# drv8305_instaspin_driver.net
KiCad netlist of a schematic drawn in Altium Designer
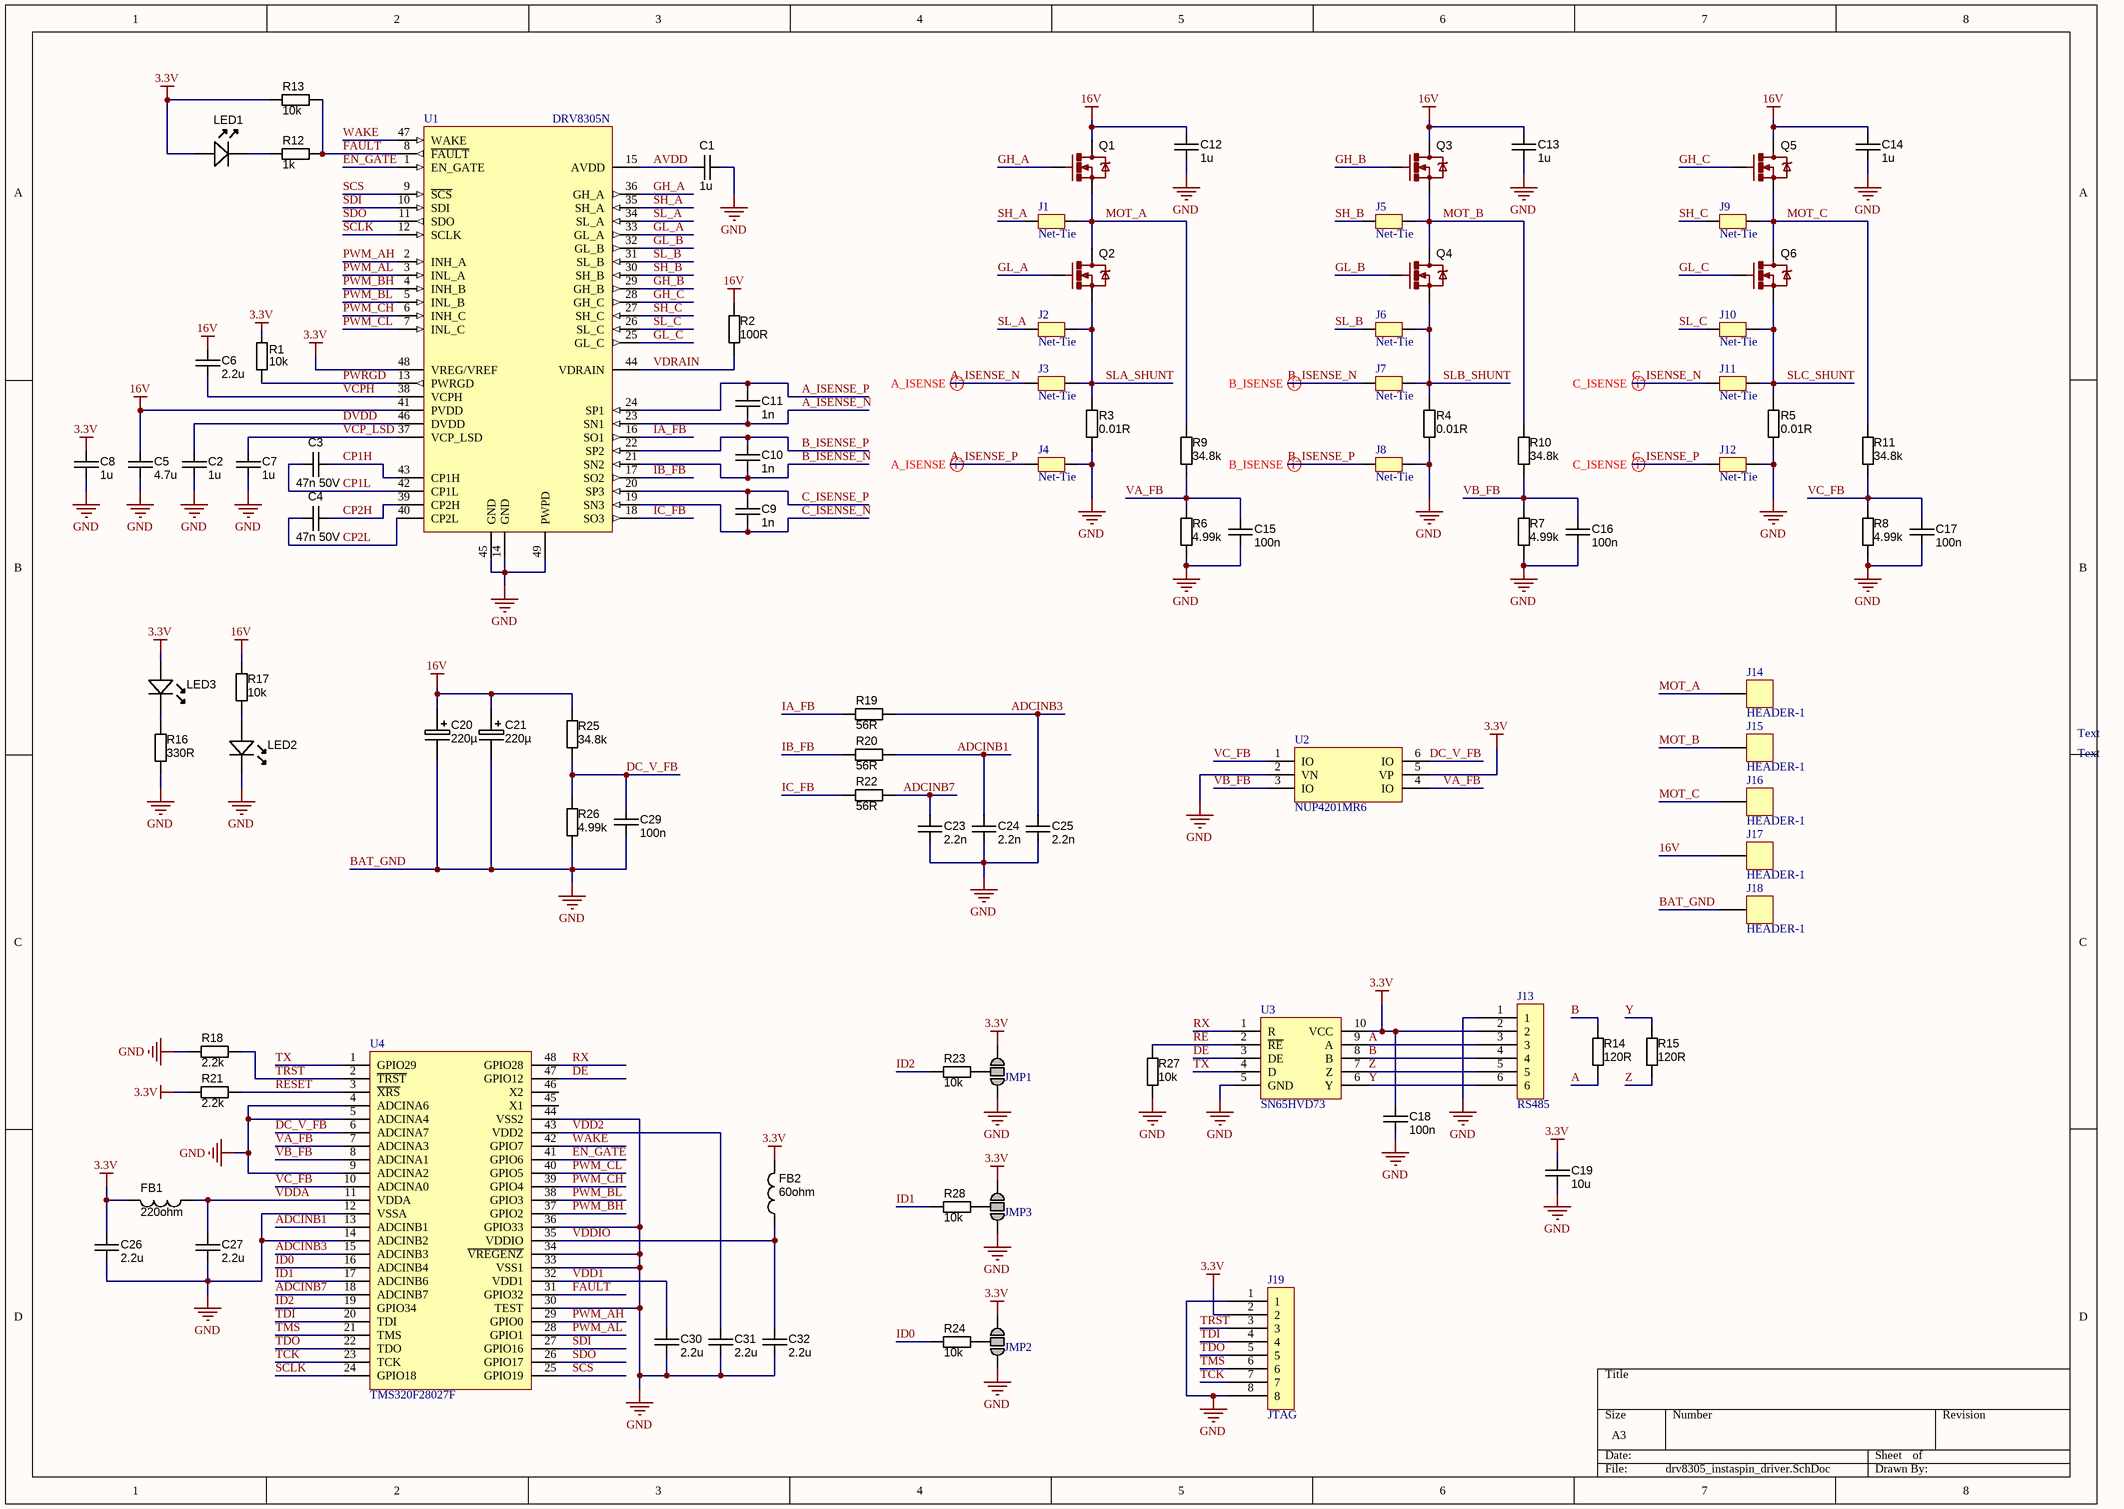
[diagram p0: drv8305_instaspin_driver.SchDoc]

(export (version "E")
  (design (tool "Eeschema 10.0.6"))
  (components
    (comp (ref "C1")
      (value "1u")
      (footprint "CAPC1608X90N")
      (description "Capacitor SMD Cer 1uF 10% 16V X7R 0603")
      (fields (field (name "TOLERANCE") "±10%"))
      (libsource (lib "PBL - Capacitors") (part "CAPC_1u_0603_X7R_16V_10%"))
    )
    (comp (ref "C2")
      (value "1u")
      (footprint "CAPC1608X90N")
      (description "Capacitor SMD Cer 1uF 10% 16V X7R 0603")
      (fields (field (name "TOLERANCE") "±10%"))
      (libsource (lib "PBL - Capacitors") (part "CAPC_1u_0603_X7R_16V_10%"))
    )
    (comp (ref "C3")
      (value "47n 50V")
      (footprint "CAPC1608X90N")
      (description "Capacitor SMD Cer 1uF 10% 16V X7R 0603")
      (fields (field (name "TOLERANCE") "±10%"))
      (libsource (lib "PBL - Capacitors") (part "CAPC_1u_0603_X7R_16V_10%"))
    )
    (comp (ref "C4")
      (value "47n 50V")
      (footprint "CAPC1608X90N")
      (description "Capacitor SMD Cer 1uF 10% 16V X7R 0603")
      (fields (field (name "TOLERANCE") "±10%"))
      (libsource (lib "PBL - Capacitors") (part "CAPC_1u_0603_X7R_16V_10%"))
    )
    (comp (ref "C5")
      (value "4.7u")
      (footprint "CAPC3216X180N")
      (description "Capacitor SMD Cer 6.8nF 5% 50V NP0 1206")
      (fields (field (name "TOLERANCE") "±5%"))
      (libsource (lib "PBL - Capacitors") (part "CAPC_6n8_1206_NP0_50V"))
    )
    (comp (ref "C6")
      (value "2.2u")
      (footprint "CAPC3216X180N")
      (description "Capacitor SMD Cer 6.8nF 5% 50V NP0 1206")
      (fields (field (name "TOLERANCE") "±5%"))
      (libsource (lib "PBL - Capacitors") (part "CAPC_6n8_1206_NP0_50V"))
    )
    (comp (ref "C7")
      (value "1u")
      (footprint "CAPC1608X90N")
      (description "Capacitor SMD Cer 1uF 10% 16V X7R 0603")
      (fields (field (name "TOLERANCE") "±10%"))
      (libsource (lib "PBL - Capacitors") (part "CAPC_1u_0603_X7R_16V_10%"))
    )
    (comp (ref "C8")
      (value "1u")
      (footprint "CAPC1608X90N")
      (description "Capacitor SMD Cer 1uF 10% 16V X7R 0603")
      (fields (field (name "TOLERANCE") "±10%"))
      (libsource (lib "PBL - Capacitors") (part "CAPC_1u_0603_X7R_16V_10%"))
    )
    (comp (ref "C9")
      (value "1n")
      (footprint "CAPC1608X90N")
      (description "Capacitor SMD Cer 1uF 10% 16V X7R 0603")
      (fields (field (name "TOLERANCE") "±10%"))
      (libsource (lib "PBL - Capacitors") (part "CAPC_1u_0603_X7R_16V_10%"))
    )
    (comp (ref "C10")
      (value "1n")
      (footprint "CAPC1608X90N")
      (description "Capacitor SMD Cer 1uF 10% 16V X7R 0603")
      (fields (field (name "TOLERANCE") "±10%"))
      (libsource (lib "PBL - Capacitors") (part "CAPC_1u_0603_X7R_16V_10%"))
    )
    (comp (ref "C11")
      (value "1n")
      (footprint "CAPC1608X90N")
      (description "Capacitor SMD Cer 1uF 10% 16V X7R 0603")
      (fields (field (name "TOLERANCE") "±10%"))
      (libsource (lib "PBL - Capacitors") (part "CAPC_1u_0603_X7R_16V_10%"))
    )
    (comp (ref "C12")
      (value "1u")
      (footprint "CAPC1608X90N")
      (description "Capacitor SMD Cer 1uF 10% 16V X7R 0603")
      (fields (field (name "TOLERANCE") "±10%"))
      (libsource (lib "PBL - Capacitors") (part "CAPC_1u_0603_X7R_16V_10%"))
    )
    (comp (ref "C13")
      (value "1u")
      (footprint "CAPC1608X90N")
      (description "Capacitor SMD Cer 1uF 10% 16V X7R 0603")
      (fields (field (name "TOLERANCE") "±10%"))
      (libsource (lib "PBL - Capacitors") (part "CAPC_1u_0603_X7R_16V_10%"))
    )
    (comp (ref "C14")
      (value "1u")
      (footprint "CAPC1608X90N")
      (description "Capacitor SMD Cer 1uF 10% 16V X7R 0603")
      (fields (field (name "TOLERANCE") "±10%"))
      (libsource (lib "PBL - Capacitors") (part "CAPC_1u_0603_X7R_16V_10%"))
    )
    (comp (ref "C15")
      (value "100n")
      (footprint "CAPC1608X90N")
      (description "Capacitor SMD Cer 1uF 10% 16V X7R 0603")
      (fields (field (name "TOLERANCE") "±10%"))
      (libsource (lib "PBL - Capacitors") (part "CAPC_1u_0603_X7R_16V_10%"))
    )
    (comp (ref "C16")
      (value "100n")
      (footprint "CAPC1608X90N")
      (description "Capacitor SMD Cer 1uF 10% 16V X7R 0603")
      (fields (field (name "TOLERANCE") "±10%"))
      (libsource (lib "PBL - Capacitors") (part "CAPC_1u_0603_X7R_16V_10%"))
    )
    (comp (ref "C17")
      (value "100n")
      (footprint "CAPC1608X90N")
      (description "Capacitor SMD Cer 1uF 10% 16V X7R 0603")
      (fields (field (name "TOLERANCE") "±10%"))
      (libsource (lib "PBL - Capacitors") (part "CAPC_1u_0603_X7R_16V_10%"))
    )
    (comp (ref "C18")
      (value "100n")
      (footprint "CAPC1608X90N")
      (description "Capacitor SMD Cer 1uF 10% 16V X7R 0603")
      (fields (field (name "TOLERANCE") "±10%"))
      (libsource (lib "PBL - Capacitors") (part "CAPC_1u_0603_X7R_16V_10%"))
    )
    (comp (ref "C19")
      (value "10u")
      (footprint "CAPC3216X180N")
      (description "Capacitor SMD Cer 1uF 10% 16V X7R 0603")
      (fields (field (name "TOLERANCE") "±10%"))
      (libsource (lib "PBL - Capacitors") (part "CAPC_1u_0603_X7R_16V_10%"))
    )
    (comp (ref "C20")
      (value "220µ")
      (footprint "CAP_ELEC_6.3x4.2")
      (description "Capacitor THT Alum Elec 470uF 20% 16V")
      (fields (field (name "TOLERANCE") "±20%"))
      (libsource (lib "PBL - Capacitors") (part "CAPE_470u_16V_THT"))
    )
    (comp (ref "C21")
      (value "220µ")
      (footprint "CAP_ELEC_6.3x4.2")
      (description "Capacitor THT Alum Elec 470uF 20% 16V")
      (fields (field (name "TOLERANCE") "±20%"))
      (libsource (lib "PBL - Capacitors") (part "CAPE_470u_16V_THT"))
    )
    (comp (ref "C23")
      (value "2.2n")
      (footprint "CAPC1608X90N")
      (description "Capacitor SMD Cer 1uF 10% 16V X7R 0603")
      (fields (field (name "TOLERANCE") "±10%"))
      (libsource (lib "PBL - Capacitors") (part "CAPC_1u_0603_X7R_16V_10%"))
    )
    (comp (ref "C24")
      (value "2.2n")
      (footprint "CAPC1608X90N")
      (description "Capacitor SMD Cer 1uF 10% 16V X7R 0603")
      (fields (field (name "TOLERANCE") "±10%"))
      (libsource (lib "PBL - Capacitors") (part "CAPC_1u_0603_X7R_16V_10%"))
    )
    (comp (ref "C25")
      (value "2.2n")
      (footprint "CAPC1608X90N")
      (description "Capacitor SMD Cer 1uF 10% 16V X7R 0603")
      (fields (field (name "TOLERANCE") "±10%"))
      (libsource (lib "PBL - Capacitors") (part "CAPC_1u_0603_X7R_16V_10%"))
    )
    (comp (ref "C26")
      (value "2.2u")
      (footprint "CAPC1608X90N")
      (description "Capacitor SMD Cer 1uF 10% 16V X7R 0603")
      (fields (field (name "TOLERANCE") "±10%"))
      (libsource (lib "PBL - Capacitors") (part "CAPC_1u_0603_X7R_16V_10%"))
    )
    (comp (ref "C27")
      (value "2.2u")
      (footprint "CAPC1608X90N")
      (description "Capacitor SMD Cer 1uF 10% 16V X7R 0603")
      (fields (field (name "TOLERANCE") "±10%"))
      (libsource (lib "PBL - Capacitors") (part "CAPC_1u_0603_X7R_16V_10%"))
    )
    (comp (ref "C29")
      (value "100n")
      (footprint "CAPC1608X90N")
      (description "Capacitor SMD Cer 1uF 10% 16V X7R 0603")
      (fields (field (name "TOLERANCE") "±10%"))
      (libsource (lib "PBL - Capacitors") (part "CAPC_1u_0603_X7R_16V_10%"))
    )
    (comp (ref "C30")
      (value "2.2u")
      (footprint "CAPC1608X90N")
      (description "Capacitor SMD Cer 1uF 10% 16V X7R 0603")
      (fields (field (name "TOLERANCE") "±10%"))
      (libsource (lib "PBL - Capacitors") (part "CAPC_1u_0603_X7R_16V_10%"))
    )
    (comp (ref "C31")
      (value "2.2u")
      (footprint "CAPC1608X90N")
      (description "Capacitor SMD Cer 1uF 10% 16V X7R 0603")
      (fields (field (name "TOLERANCE") "±10%"))
      (libsource (lib "PBL - Capacitors") (part "CAPC_1u_0603_X7R_16V_10%"))
    )
    (comp (ref "C32")
      (value "2.2u")
      (footprint "CAPC1608X90N")
      (description "Capacitor SMD Cer 1uF 10% 16V X7R 0603")
      (fields (field (name "TOLERANCE") "±10%"))
      (libsource (lib "PBL - Capacitors") (part "CAPC_1u_0603_X7R_16V_10%"))
    )
    (comp (ref "FB1")
      (value "220ohm")
      (footprint "INDC1608N")
      (description "Ferrite bead 120 Ohm at 100 MHz 2A 0603 SMD")
      (libsource (lib "PBL - Inductors") (part "FERRITE_120R-100MHz_0603"))
    )
    (comp (ref "FB2")
      (value "60ohm")
      (footprint "INDC1608N")
      (description "Ferrite bead 120 Ohm at 100 MHz 2A 0603 SMD")
      (libsource (lib "PBL - Inductors") (part "FERRITE_120R-100MHz_0603"))
    )
    (comp (ref "J1")
      (value "Net-Tie")
      (footprint "NET-TIE-0602")
      (libsource (lib "connectors") (part "Net-Tie"))
    )
    (comp (ref "J2")
      (value "Net-Tie")
      (footprint "NET-TIE-0602")
      (libsource (lib "connectors") (part "Net-Tie"))
    )
    (comp (ref "J3")
      (value "Net-Tie")
      (footprint "NET-TIE-0602")
      (libsource (lib "connectors") (part "Net-Tie"))
    )
    (comp (ref "J4")
      (value "Net-Tie")
      (footprint "NET-TIE-0602")
      (libsource (lib "connectors") (part "Net-Tie"))
    )
    (comp (ref "J5")
      (value "Net-Tie")
      (footprint "NET-TIE-0602")
      (libsource (lib "connectors") (part "Net-Tie"))
    )
    (comp (ref "J6")
      (value "Net-Tie")
      (footprint "NET-TIE-0602")
      (libsource (lib "connectors") (part "Net-Tie"))
    )
    (comp (ref "J7")
      (value "Net-Tie")
      (footprint "NET-TIE-0602")
      (libsource (lib "connectors") (part "Net-Tie"))
    )
    (comp (ref "J8")
      (value "Net-Tie")
      (footprint "NET-TIE-0602")
      (libsource (lib "connectors") (part "Net-Tie"))
    )
    (comp (ref "J9")
      (value "Net-Tie")
      (footprint "NET-TIE-0602")
      (libsource (lib "connectors") (part "Net-Tie"))
    )
    (comp (ref "J10")
      (value "Net-Tie")
      (footprint "NET-TIE-0602")
      (libsource (lib "connectors") (part "Net-Tie"))
    )
    (comp (ref "J11")
      (value "Net-Tie")
      (footprint "NET-TIE-0602")
      (libsource (lib "connectors") (part "Net-Tie"))
    )
    (comp (ref "J12")
      (value "Net-Tie")
      (footprint "NET-TIE-0602")
      (libsource (lib "connectors") (part "Net-Tie"))
    )
    (comp (ref "J13")
      (value "RS485")
      (footprint "MICRO-MATCH-6")
      (libsource (lib "connectors") (part "HEADER-6"))
    )
    (comp (ref "J14")
      (value "HEADER-1")
      (footprint "2MM-BANANA-VIA-BOTTOM-PAD")
      (libsource (lib "connectors") (part "HEADER-1"))
    )
    (comp (ref "J15")
      (value "HEADER-1")
      (footprint "2MM-BANANA-VIA-BOTTOM-PAD")
      (libsource (lib "connectors") (part "HEADER-1"))
    )
    (comp (ref "J16")
      (value "HEADER-1")
      (footprint "2MM-BANANA-VIA-BOTTOM-PAD")
      (libsource (lib "connectors") (part "HEADER-1"))
    )
    (comp (ref "J17")
      (value "HEADER-1")
      (footprint "2MM-BANANA-VIA-BOTTOM-PAD")
      (libsource (lib "connectors") (part "HEADER-1"))
    )
    (comp (ref "J18")
      (value "HEADER-1")
      (footprint "2MM-BANANA-VIA-BOTTOM-PAD")
      (libsource (lib "connectors") (part "HEADER-1"))
    )
    (comp (ref "J19")
      (value "JTAG")
      (footprint "MICRO-MATCH-8")
      (libsource (lib "connectors") (part "HEADER-8"))
    )
    (comp (ref "JMP1")
      (value "JUMPER")
      (footprint "JUMPER-SMD-3WAY-0303")
      (libsource (lib "connectors") (part "JUMPER-SMD-3WAY"))
    )
    (comp (ref "JMP2")
      (value "JUMPER")
      (footprint "JUMPER-SMD-3WAY-0303")
      (libsource (lib "connectors") (part "JUMPER-SMD-3WAY"))
    )
    (comp (ref "JMP3")
      (value "JUMPER")
      (footprint "JUMPER-SMD-3WAY-0303")
      (libsource (lib "connectors") (part "JUMPER-SMD-3WAY"))
    )
    (comp (ref "LED1")
      (value "LED Orange")
      (footprint "LED-0603-GREEN")
      (description "LED 0603 SMD Green 525nm 350mcd 20mA")
      (libsource (lib "PBL - Light Sources") (part "LED_SMD_Green_0603_525nm_350mcd"))
    )
    (comp (ref "LED2")
      (value "LED White")
      (footprint "LED-0603-GREEN")
      (description "LED 0603 SMD Green 525nm 350mcd 20mA")
      (libsource (lib "PBL - Light Sources") (part "LED_SMD_Green_0603_525nm_350mcd"))
    )
    (comp (ref "LED3")
      (value "LED White")
      (footprint "LED-0603-GREEN")
      (description "LED 0603 SMD Green 525nm 350mcd 20mA")
      (libsource (lib "PBL - Light Sources") (part "LED_SMD_Green_0603_525nm_350mcd"))
    )
    (comp (ref "Q1") (value "MOSFET-N") (footprint "SOT669") (libsource (lib "mosfets") (part "MOSFET-N")))
    (comp (ref "Q2") (value "MOSFET-N") (footprint "SOT669") (libsource (lib "mosfets") (part "MOSFET-N")))
    (comp (ref "Q3") (value "MOSFET-N") (footprint "SOT669") (libsource (lib "mosfets") (part "MOSFET-N")))
    (comp (ref "Q4") (value "MOSFET-N") (footprint "SOT669") (libsource (lib "mosfets") (part "MOSFET-N")))
    (comp (ref "Q5") (value "MOSFET-N") (footprint "SOT669") (libsource (lib "mosfets") (part "MOSFET-N")))
    (comp (ref "Q6") (value "MOSFET-N") (footprint "SOT669") (libsource (lib "mosfets") (part "MOSFET-N")))
    (comp (ref "R1")
      (value "10k")
      (footprint "RESC1608X55N")
      (description "Resistor SMD chip 1.5k Ohm 0.1W 5% 0603")
      (fields (field (name "TOLERANCE") "±5%"))
      (libsource (lib "") (part "RES_1K5_0603_5%_3"))
    )
    (comp (ref "R2")
      (value "100R")
      (footprint "RESC1608X55N")
      (description "Resistor SMD chip 1.5k Ohm 0.1W 5% 0603")
      (fields (field (name "TOLERANCE") "±5%"))
      (libsource (lib "PBL - Resistors") (part "RES_1K5_0603_5%"))
    )
    (comp (ref "R3")
      (value "0.01R")
      (footprint "RESC6332X70N")
      (description "Resistor SMD chip 3.3k Ohm 1W 5% 2512")
      (fields (field (name "TOLERANCE") "±5%"))
      (libsource (lib "PBL - Resistors") (part "RES_3K3_2512_5%"))
    )
    (comp (ref "R4")
      (value "0.01R")
      (footprint "RESC6332X70N")
      (description "Resistor SMD chip 3.3k Ohm 1W 5% 2512")
      (fields (field (name "TOLERANCE") "±5%"))
      (libsource (lib "PBL - Resistors") (part "RES_3K3_2512_5%"))
    )
    (comp (ref "R5")
      (value "0.01R")
      (footprint "RESC6332X70N")
      (description "Resistor SMD chip 3.3k Ohm 1W 5% 2512")
      (fields (field (name "TOLERANCE") "±5%"))
      (libsource (lib "PBL - Resistors") (part "RES_3K3_2512_5%"))
    )
    (comp (ref "R6")
      (value "4.99k")
      (footprint "RESC1608X55N")
      (description "Resistor SMD chip 1.5k Ohm 0.1W 5% 0603")
      (fields (field (name "TOLERANCE") "±5%"))
      (libsource (lib "PBL - Resistors") (part "RES_1K5_0603_5%"))
    )
    (comp (ref "R7")
      (value "4.99k")
      (footprint "RESC1608X55N")
      (description "Resistor SMD chip 1.5k Ohm 0.1W 5% 0603")
      (fields (field (name "TOLERANCE") "±5%"))
      (libsource (lib "PBL - Resistors") (part "RES_1K5_0603_5%"))
    )
    (comp (ref "R8")
      (value "4.99k")
      (footprint "RESC1608X55N")
      (description "Resistor SMD chip 1.5k Ohm 0.1W 5% 0603")
      (fields (field (name "TOLERANCE") "±5%"))
      (libsource (lib "PBL - Resistors") (part "RES_1K5_0603_5%"))
    )
    (comp (ref "R9")
      (value "34.8k")
      (footprint "RESC1608X55N")
      (description "Resistor SMD chip 1.5k Ohm 0.1W 5% 0603")
      (fields (field (name "TOLERANCE") "±5%"))
      (libsource (lib "PBL - Resistors") (part "RES_1K5_0603_5%"))
    )
    (comp (ref "R10")
      (value "34.8k")
      (footprint "RESC1608X55N")
      (description "Resistor SMD chip 1.5k Ohm 0.1W 5% 0603")
      (fields (field (name "TOLERANCE") "±5%"))
      (libsource (lib "PBL - Resistors") (part "RES_1K5_0603_5%"))
    )
    (comp (ref "R11")
      (value "34.8k")
      (footprint "RESC1608X55N")
      (description "Resistor SMD chip 1.5k Ohm 0.1W 5% 0603")
      (fields (field (name "TOLERANCE") "±5%"))
      (libsource (lib "PBL - Resistors") (part "RES_1K5_0603_5%"))
    )
    (comp (ref "R12")
      (value "1k")
      (footprint "RESC1608X55N")
      (description "Resistor SMD chip 1.5k Ohm 0.1W 5% 0603")
      (fields (field (name "TOLERANCE") "±5%"))
      (libsource (lib "") (part "RES_1K5_0603_5%_2"))
    )
    (comp (ref "R13")
      (value "10k")
      (footprint "RESC1608X55N")
      (description "Resistor SMD chip 1.5k Ohm 0.1W 5% 0603")
      (fields (field (name "TOLERANCE") "±5%"))
      (libsource (lib "") (part "RES_1K5_0603_5%_2"))
    )
    (comp (ref "R14")
      (value "120R")
      (footprint "RESC1608X55N")
      (description "Resistor SMD chip 1.5k Ohm 0.1W 5% 0603")
      (fields (field (name "TOLERANCE") "±5%"))
      (libsource (lib "PBL - Resistors") (part "RES_1K5_0603_5%"))
    )
    (comp (ref "R15")
      (value "120R")
      (footprint "RESC1608X55N")
      (description "Resistor SMD chip 1.5k Ohm 0.1W 5% 0603")
      (fields (field (name "TOLERANCE") "±5%"))
      (libsource (lib "PBL - Resistors") (part "RES_1K5_0603_5%"))
    )
    (comp (ref "R16")
      (value "330R")
      (footprint "RESC1608X55N")
      (description "Resistor SMD chip 1.5k Ohm 0.1W 5% 0603")
      (fields (field (name "TOLERANCE") "±5%"))
      (libsource (lib "PBL - Resistors") (part "RES_1K5_0603_5%"))
    )
    (comp (ref "R17")
      (value "10k")
      (footprint "RESC1608X55N")
      (description "Resistor SMD chip 1.5k Ohm 0.1W 5% 0603")
      (fields (field (name "TOLERANCE") "±5%"))
      (libsource (lib "PBL - Resistors") (part "RES_1K5_0603_5%"))
    )
    (comp (ref "R18")
      (value "2.2k")
      (footprint "RESC1608X55N")
      (description "Resistor SMD chip 1.5k Ohm 0.1W 5% 0603")
      (fields (field (name "TOLERANCE") "±5%"))
      (libsource (lib "") (part "RES_1K5_0603_5%_2"))
    )
    (comp (ref "R19")
      (value "56R")
      (footprint "RESC1608X55N")
      (description "Resistor SMD chip 1.5k Ohm 0.1W 5% 0603")
      (fields (field (name "TOLERANCE") "±5%"))
      (libsource (lib "") (part "RES_1K5_0603_5%_1"))
    )
    (comp (ref "R20")
      (value "56R")
      (footprint "RESC1608X55N")
      (description "Resistor SMD chip 1.5k Ohm 0.1W 5% 0603")
      (fields (field (name "TOLERANCE") "±5%"))
      (libsource (lib "") (part "RES_1K5_0603_5%_1"))
    )
    (comp (ref "R21")
      (value "2.2k")
      (footprint "RESC1608X55N")
      (description "Resistor SMD chip 1.5k Ohm 0.1W 5% 0603")
      (fields (field (name "TOLERANCE") "±5%"))
      (libsource (lib "") (part "RES_1K5_0603_5%_1"))
    )
    (comp (ref "R22")
      (value "56R")
      (footprint "RESC1608X55N")
      (description "Resistor SMD chip 1.5k Ohm 0.1W 5% 0603")
      (fields (field (name "TOLERANCE") "±5%"))
      (libsource (lib "") (part "RES_1K5_0603_5%_1"))
    )
    (comp (ref "R23")
      (value "10k")
      (footprint "RESC1608X55N")
      (description "Resistor SMD chip 1.5k Ohm 0.1W 5% 0603")
      (fields (field (name "TOLERANCE") "±5%"))
      (libsource (lib "") (part "RES_1K5_0603_5%_1"))
    )
    (comp (ref "R24")
      (value "10k")
      (footprint "RESC1608X55N")
      (description "Resistor SMD chip 1.5k Ohm 0.1W 5% 0603")
      (fields (field (name "TOLERANCE") "±5%"))
      (libsource (lib "") (part "RES_1K5_0603_5%_1"))
    )
    (comp (ref "R25")
      (value "34.8k")
      (footprint "RESC1608X55N")
      (description "Resistor SMD chip 1.5k Ohm 0.1W 5% 0603")
      (fields (field (name "TOLERANCE") "±5%"))
      (libsource (lib "PBL - Resistors") (part "RES_1K5_0603_5%"))
    )
    (comp (ref "R26")
      (value "4.99k")
      (footprint "RESC1608X55N")
      (description "Resistor SMD chip 1.5k Ohm 0.1W 5% 0603")
      (fields (field (name "TOLERANCE") "±5%"))
      (libsource (lib "PBL - Resistors") (part "RES_1K5_0603_5%"))
    )
    (comp (ref "R27")
      (value "10k")
      (footprint "RESC1608X55N")
      (description "Resistor SMD chip 1.5k Ohm 0.1W 5% 0603")
      (fields (field (name "TOLERANCE") "±5%"))
      (libsource (lib "") (part "RES_1K5_0603_5%_3"))
    )
    (comp (ref "R28")
      (value "10k")
      (footprint "RESC1608X55N")
      (description "Resistor SMD chip 1.5k Ohm 0.1W 5% 0603")
      (fields (field (name "TOLERANCE") "±5%"))
      (libsource (lib "") (part "RES_1K5_0603_5%_1"))
    )
    (comp (ref "U1")
      (value "DRV8305N")
      (footprint "PQFP48_PAD")
      (libsource (lib "texas_instruments") (part "DRV8305"))
    )
    (comp (ref "U2")
      (value "NUP4201MR6")
      (footprint "TSOP-6")
      (libsource (lib "digital") (part "NUP4201MR6"))
    )
    (comp (ref "U3")
      (value "SN65HVD73")
      (footprint "SOP10")
      (libsource (lib "texas_instruments") (part "SN65HVD3086E"))
    )
    (comp (ref "U4")
      (value "TMS320F28027F")
      (footprint "PQFP48")
      (libsource (lib "texas_instruments") (part "TMS320F28027F"))
    )
  )
  (nets
    (net (code "1") (name "/A") (class "Default")
      (node (ref "J13") (pin "3") (pinfunction "3_3") (pintype "passive"))
      (node (ref "R14") (pin "1") (pinfunction "1_1") (pintype "passive"))
      (node (ref "U3") (pin "9") (pinfunction "A_9") (pintype "passive"))
    )
    (net (code "2") (name "/ADCINB1") (class "Default")
      (node (ref "C24") (pin "1") (pintype "passive"))
      (node (ref "R20") (pin "1") (pinfunction "1_1") (pintype "passive"))
      (node (ref "U4") (pin "13") (pinfunction "ADCINB1_13") (pintype "passive"))
    )
    (net (code "3") (name "/ADCINB3") (class "Default")
      (node (ref "C25") (pin "1") (pintype "passive"))
      (node (ref "R19") (pin "1") (pinfunction "1_1") (pintype "passive"))
      (node (ref "U4") (pin "15") (pinfunction "ADCINB3_15") (pintype "passive"))
    )
    (net (code "4") (name "/ADCINB7") (class "Default")
      (node (ref "C23") (pin "1") (pintype "passive"))
      (node (ref "R22") (pin "1") (pinfunction "1_1") (pintype "passive"))
      (node (ref "U4") (pin "18") (pinfunction "ADCINB7_18") (pintype "passive"))
    )
    (net (code "5") (name "/AVDD") (class "Default")
      (node (ref "C1") (pin "2") (pintype "passive"))
      (node (ref "U1") (pin "15") (pinfunction "AVDD_15") (pintype "power_in"))
    )
    (net (code "6") (name "/A_ISENSE_N") (class "Default")
      (node (ref "C11") (pin "1") (pintype "passive"))
      (node (ref "J3") (pin "1") (pinfunction "1_1") (pintype "passive"))
      (node (ref "U1") (pin "23") (pinfunction "SN1_23") (pintype "input"))
    )
    (net (code "7") (name "/A_ISENSE_P") (class "Default")
      (node (ref "C11") (pin "2") (pintype "passive"))
      (node (ref "J4") (pin "1") (pinfunction "1_1") (pintype "passive"))
      (node (ref "U1") (pin "24") (pinfunction "SP1_24") (pintype "input"))
    )
    (net (code "8") (name "/B") (class "Default")
      (node (ref "J13") (pin "4") (pinfunction "4_4") (pintype "passive"))
      (node (ref "R14") (pin "2") (pinfunction "2_2") (pintype "passive"))
      (node (ref "U3") (pin "8") (pinfunction "B_8") (pintype "passive"))
    )
    (net (code "9") (name "/B_ISENSE_N") (class "Default")
      (node (ref "C10") (pin "1") (pintype "passive"))
      (node (ref "J7") (pin "1") (pinfunction "1_1") (pintype "passive"))
      (node (ref "U1") (pin "21") (pinfunction "SN2_21") (pintype "input"))
    )
    (net (code "10") (name "/B_ISENSE_P") (class "Default")
      (node (ref "C10") (pin "2") (pintype "passive"))
      (node (ref "J8") (pin "1") (pinfunction "1_1") (pintype "passive"))
      (node (ref "U1") (pin "22") (pinfunction "SP2_22") (pintype "input"))
    )
    (net (code "11") (name "/CP1H") (class "Default")
      (node (ref "C3") (pin "1") (pintype "passive"))
      (node (ref "U1") (pin "43") (pinfunction "CP1H_43") (pintype "power_in"))
    )
    (net (code "12") (name "/CP1L") (class "Default")
      (node (ref "C3") (pin "2") (pintype "passive"))
      (node (ref "U1") (pin "42") (pinfunction "CP1L_42") (pintype "power_in"))
    )
    (net (code "13") (name "/CP2H") (class "Default")
      (node (ref "C4") (pin "1") (pintype "passive"))
      (node (ref "U1") (pin "39") (pinfunction "CP2H_39") (pintype "power_in"))
    )
    (net (code "14") (name "/CP2L") (class "Default")
      (node (ref "C4") (pin "2") (pintype "passive"))
      (node (ref "U1") (pin "40") (pinfunction "CP2L_40") (pintype "power_in"))
    )
    (net (code "15") (name "/C_ISENSE_N") (class "Default")
      (node (ref "C9") (pin "1") (pintype "passive"))
      (node (ref "J11") (pin "1") (pinfunction "1_1") (pintype "passive"))
      (node (ref "U1") (pin "19") (pinfunction "SN3_19") (pintype "input"))
    )
    (net (code "16") (name "/C_ISENSE_P") (class "Default")
      (node (ref "C9") (pin "2") (pintype "passive"))
      (node (ref "J12") (pin "1") (pinfunction "1_1") (pintype "passive"))
      (node (ref "U1") (pin "20") (pinfunction "SP3_20") (pintype "input"))
    )
    (net (code "17") (name "/DC_V_FB") (class "Default")
      (node (ref "C29") (pin "1") (pintype "passive"))
      (node (ref "R25") (pin "1") (pinfunction "1_1") (pintype "passive"))
      (node (ref "R26") (pin "2") (pinfunction "2_2") (pintype "passive"))
      (node (ref "U2") (pin "6") (pinfunction "IO_6") (pintype "passive"))
      (node (ref "U4") (pin "6") (pinfunction "ADCINA7_6") (pintype "passive"))
    )
    (net (code "18") (name "/DE") (class "Default")
      (node (ref "U3") (pin "3") (pinfunction "DE_3") (pintype "passive"))
      (node (ref "U4") (pin "47") (pinfunction "GPIO12_47") (pintype "passive"))
    )
    (net (code "19") (name "/DVDD") (class "Default")
      (node (ref "C2") (pin "2") (pintype "passive"))
      (node (ref "U1") (pin "46") (pinfunction "DVDD_46") (pintype "power_in"))
    )
    (net (code "20") (name "/EN_GATE") (class "Default")
      (node (ref "U1") (pin "1") (pinfunction "EN_GATE_1") (pintype "input"))
      (node (ref "U4") (pin "41") (pinfunction "GPIO6_41") (pintype "passive"))
    )
    (net (code "21") (name "/FAULT") (class "Default")
      (node (ref "R12") (pin "2") (pinfunction "2_2") (pintype "passive"))
      (node (ref "R13") (pin "2") (pinfunction "2_2") (pintype "passive"))
      (node (ref "U1") (pin "8") (pinfunction "~{FAULT}_8") (pintype "output"))
      (node (ref "U4") (pin "31") (pinfunction "GPIO32_31") (pintype "passive"))
    )
    (net (code "22") (name "/GH_A") (class "Default")
      (node (ref "Q1") (pin "G") (pinfunction "G_G") (pintype "passive"))
      (node (ref "U1") (pin "36") (pinfunction "GH_A_36") (pintype "output"))
    )
    (net (code "23") (name "/GH_B") (class "Default")
      (node (ref "Q3") (pin "G") (pinfunction "G_G") (pintype "passive"))
      (node (ref "U1") (pin "29") (pinfunction "GH_B_29") (pintype "output"))
    )
    (net (code "24") (name "/GH_C") (class "Default")
      (node (ref "Q5") (pin "G") (pinfunction "G_G") (pintype "passive"))
      (node (ref "U1") (pin "28") (pinfunction "GH_C_28") (pintype "output"))
    )
    (net (code "25") (name "/GL_A") (class "Default")
      (node (ref "Q2") (pin "G") (pinfunction "G_G") (pintype "passive"))
      (node (ref "U1") (pin "33") (pinfunction "GL_A_33") (pintype "output"))
    )
    (net (code "26") (name "/GL_B") (class "Default")
      (node (ref "Q4") (pin "G") (pinfunction "G_G") (pintype "passive"))
      (node (ref "U1") (pin "32") (pinfunction "GL_B_32") (pintype "output"))
    )
    (net (code "27") (name "/GL_C") (class "Default")
      (node (ref "Q6") (pin "G") (pinfunction "G_G") (pintype "passive"))
      (node (ref "U1") (pin "25") (pinfunction "GL_C_25") (pintype "output"))
    )
    (net (code "28") (name "/IA_FB") (class "Default")
      (node (ref "R19") (pin "2") (pinfunction "2_2") (pintype "passive"))
      (node (ref "U1") (pin "16") (pinfunction "SO1_16") (pintype "output"))
    )
    (net (code "29") (name "/IB_FB") (class "Default")
      (node (ref "R20") (pin "2") (pinfunction "2_2") (pintype "passive"))
      (node (ref "U1") (pin "17") (pinfunction "SO2_17") (pintype "output"))
    )
    (net (code "30") (name "/IC_FB") (class "Default")
      (node (ref "R22") (pin "2") (pinfunction "2_2") (pintype "passive"))
      (node (ref "U1") (pin "18") (pinfunction "SO3_18") (pintype "output"))
    )
    (net (code "31") (name "/ID0") (class "Default")
      (node (ref "R24") (pin "2") (pinfunction "2_2") (pintype "passive"))
      (node (ref "U4") (pin "16") (pinfunction "ADCINB4_16") (pintype "passive"))
    )
    (net (code "32") (name "/ID1") (class "Default")
      (node (ref "R28") (pin "2") (pinfunction "2_2") (pintype "passive"))
      (node (ref "U4") (pin "17") (pinfunction "ADCINB6_17") (pintype "passive"))
    )
    (net (code "33") (name "/ID2") (class "Default")
      (node (ref "R23") (pin "2") (pinfunction "2_2") (pintype "passive"))
      (node (ref "U4") (pin "19") (pinfunction "GPIO34_19") (pintype "passive"))
    )
    (net (code "34") (name "/MOT_A") (class "Default")
      (node (ref "J1") (pin "2") (pinfunction "2_2") (pintype "passive"))
      (node (ref "J14") (pin "1") (pinfunction "1_1") (pintype "passive"))
      (node (ref "Q1") (pin "S") (pinfunction "S_S") (pintype "passive"))
      (node (ref "Q2") (pin "D") (pinfunction "D_D") (pintype "passive"))
      (node (ref "R9") (pin "2") (pinfunction "2_2") (pintype "passive"))
    )
    (net (code "35") (name "/MOT_B") (class "Default")
      (node (ref "J15") (pin "1") (pinfunction "1_1") (pintype "passive"))
      (node (ref "J5") (pin "2") (pinfunction "2_2") (pintype "passive"))
      (node (ref "Q3") (pin "S") (pinfunction "S_S") (pintype "passive"))
      (node (ref "Q4") (pin "D") (pinfunction "D_D") (pintype "passive"))
      (node (ref "R10") (pin "2") (pinfunction "2_2") (pintype "passive"))
    )
    (net (code "36") (name "/MOT_C") (class "Default")
      (node (ref "J16") (pin "1") (pinfunction "1_1") (pintype "passive"))
      (node (ref "J9") (pin "2") (pinfunction "2_2") (pintype "passive"))
      (node (ref "Q5") (pin "S") (pinfunction "S_S") (pintype "passive"))
      (node (ref "Q6") (pin "D") (pinfunction "D_D") (pintype "passive"))
      (node (ref "R11") (pin "2") (pinfunction "2_2") (pintype "passive"))
    )
    (net (code "37") (name "/PWM_AH") (class "Default")
      (node (ref "U1") (pin "2") (pinfunction "INH_A_2") (pintype "input"))
      (node (ref "U4") (pin "29") (pinfunction "GPIO0_29") (pintype "passive"))
    )
    (net (code "38") (name "/PWM_AL") (class "Default")
      (node (ref "U1") (pin "3") (pinfunction "INL_A_3") (pintype "input"))
      (node (ref "U4") (pin "28") (pinfunction "GPIO1_28") (pintype "passive"))
    )
    (net (code "39") (name "/PWM_BH") (class "Default")
      (node (ref "U1") (pin "4") (pinfunction "INH_B_4") (pintype "input"))
      (node (ref "U4") (pin "37") (pinfunction "GPIO2_37") (pintype "passive"))
    )
    (net (code "40") (name "/PWM_BL") (class "Default")
      (node (ref "U1") (pin "5") (pinfunction "INL_B_5") (pintype "input"))
      (node (ref "U4") (pin "38") (pinfunction "GPIO3_38") (pintype "passive"))
    )
    (net (code "41") (name "/PWM_CH") (class "Default")
      (node (ref "U1") (pin "6") (pinfunction "INH_C_6") (pintype "input"))
      (node (ref "U4") (pin "39") (pinfunction "GPIO4_39") (pintype "passive"))
    )
    (net (code "42") (name "/PWM_CL") (class "Default")
      (node (ref "U1") (pin "7") (pinfunction "INL_C_7") (pintype "input"))
      (node (ref "U4") (pin "40") (pinfunction "GPIO5_40") (pintype "passive"))
    )
    (net (code "43") (name "/PWRGD") (class "Default")
      (node (ref "R1") (pin "2") (pinfunction "2_2") (pintype "passive"))
      (node (ref "U1") (pin "13") (pinfunction "PWRGD_13") (pintype "output"))
    )
    (net (code "44") (name "/RE") (class "Default")
      (node (ref "R27") (pin "1") (pinfunction "1_1") (pintype "passive"))
      (node (ref "U3") (pin "2") (pinfunction "~{RE}_2") (pintype "passive"))
    )
    (net (code "45") (name "/RESET") (class "Default")
      (node (ref "R21") (pin "1") (pinfunction "1_1") (pintype "passive"))
      (node (ref "U4") (pin "3") (pinfunction "~{XRS}_3") (pintype "passive"))
    )
    (net (code "46") (name "/RX") (class "Default")
      (node (ref "U3") (pin "1") (pinfunction "R_1") (pintype "passive"))
      (node (ref "U4") (pin "48") (pinfunction "GPIO28_48") (pintype "passive"))
    )
    (net (code "47") (name "/SCLK") (class "Default")
      (node (ref "U1") (pin "12") (pinfunction "SCLK_12") (pintype "input"))
      (node (ref "U4") (pin "24") (pinfunction "GPIO18_24") (pintype "passive"))
    )
    (net (code "48") (name "/SCS") (class "Default")
      (node (ref "U1") (pin "9") (pinfunction "~{SCS}_9") (pintype "input"))
      (node (ref "U4") (pin "25") (pinfunction "GPIO19_25") (pintype "passive"))
    )
    (net (code "49") (name "/SDI") (class "Default")
      (node (ref "U1") (pin "10") (pinfunction "SDI_10") (pintype "input"))
      (node (ref "U4") (pin "27") (pinfunction "GPIO16_27") (pintype "passive"))
    )
    (net (code "50") (name "/SDO") (class "Default")
      (node (ref "U1") (pin "11") (pinfunction "SDO_11") (pintype "output"))
      (node (ref "U4") (pin "26") (pinfunction "GPIO17_26") (pintype "passive"))
    )
    (net (code "51") (name "/SH_A") (class "Default")
      (node (ref "J1") (pin "1") (pinfunction "1_1") (pintype "passive"))
      (node (ref "U1") (pin "35") (pinfunction "SH_A_35") (pintype "input"))
    )
    (net (code "52") (name "/SH_B") (class "Default")
      (node (ref "J5") (pin "1") (pinfunction "1_1") (pintype "passive"))
      (node (ref "U1") (pin "30") (pinfunction "SH_B_30") (pintype "input"))
    )
    (net (code "53") (name "/SH_C") (class "Default")
      (node (ref "J9") (pin "1") (pinfunction "1_1") (pintype "passive"))
      (node (ref "U1") (pin "27") (pinfunction "SH_C_27") (pintype "input"))
    )
    (net (code "54") (name "/SLA_SHUNT") (class "Default")
      (node (ref "J2") (pin "2") (pinfunction "2_2") (pintype "passive"))
      (node (ref "J3") (pin "2") (pinfunction "2_2") (pintype "passive"))
      (node (ref "Q2") (pin "S") (pinfunction "S_S") (pintype "passive"))
      (node (ref "R3") (pin "1") (pinfunction "1_1") (pintype "passive"))
    )
    (net (code "55") (name "/SLB_SHUNT") (class "Default")
      (node (ref "J6") (pin "2") (pinfunction "2_2") (pintype "passive"))
      (node (ref "J7") (pin "2") (pinfunction "2_2") (pintype "passive"))
      (node (ref "Q4") (pin "S") (pinfunction "S_S") (pintype "passive"))
      (node (ref "R4") (pin "1") (pinfunction "1_1") (pintype "passive"))
    )
    (net (code "56") (name "/SLC_SHUNT") (class "Default")
      (node (ref "J10") (pin "2") (pinfunction "2_2") (pintype "passive"))
      (node (ref "J11") (pin "2") (pinfunction "2_2") (pintype "passive"))
      (node (ref "Q6") (pin "S") (pinfunction "S_S") (pintype "passive"))
      (node (ref "R5") (pin "1") (pinfunction "1_1") (pintype "passive"))
    )
    (net (code "57") (name "/SL_A") (class "Default")
      (node (ref "J2") (pin "1") (pinfunction "1_1") (pintype "passive"))
      (node (ref "U1") (pin "34") (pinfunction "SL_A_34") (pintype "input"))
    )
    (net (code "58") (name "/SL_B") (class "Default")
      (node (ref "J6") (pin "1") (pinfunction "1_1") (pintype "passive"))
      (node (ref "U1") (pin "31") (pinfunction "SL_B_31") (pintype "input"))
    )
    (net (code "59") (name "/SL_C") (class "Default")
      (node (ref "J10") (pin "1") (pinfunction "1_1") (pintype "passive"))
      (node (ref "U1") (pin "26") (pinfunction "SL_C_26") (pintype "input"))
    )
    (net (code "60") (name "/TCK") (class "Default")
      (node (ref "J19") (pin "7") (pinfunction "7_7") (pintype "passive"))
      (node (ref "U4") (pin "23") (pinfunction "TCK_23") (pintype "passive"))
    )
    (net (code "61") (name "/TDI") (class "Default")
      (node (ref "J19") (pin "4") (pinfunction "4_4") (pintype "passive"))
      (node (ref "U4") (pin "20") (pinfunction "TDI_20") (pintype "passive"))
    )
    (net (code "62") (name "/TDO") (class "Default")
      (node (ref "J19") (pin "5") (pinfunction "5_5") (pintype "passive"))
      (node (ref "U4") (pin "22") (pinfunction "TDO_22") (pintype "passive"))
    )
    (net (code "63") (name "/TMS") (class "Default")
      (node (ref "J19") (pin "6") (pinfunction "6_6") (pintype "passive"))
      (node (ref "U4") (pin "21") (pinfunction "TMS_21") (pintype "passive"))
    )
    (net (code "64") (name "/TRST") (class "Default")
      (node (ref "J19") (pin "3") (pinfunction "3_3") (pintype "passive"))
      (node (ref "R18") (pin "2") (pinfunction "2_2") (pintype "passive"))
      (node (ref "U4") (pin "2") (pinfunction "~{TRST}_2") (pintype "passive"))
    )
    (net (code "65") (name "/TX") (class "Default")
      (node (ref "U3") (pin "4") (pinfunction "D_4") (pintype "passive"))
      (node (ref "U4") (pin "1") (pinfunction "GPIO29_1") (pintype "passive"))
    )
    (net (code "66") (name "/VA_FB") (class "Default")
      (node (ref "C15") (pin "1") (pintype "passive"))
      (node (ref "R6") (pin "2") (pinfunction "2_2") (pintype "passive"))
      (node (ref "R9") (pin "1") (pinfunction "1_1") (pintype "passive"))
      (node (ref "U2") (pin "4") (pinfunction "IO_4") (pintype "passive"))
      (node (ref "U4") (pin "7") (pinfunction "ADCINA3_7") (pintype "passive"))
    )
    (net (code "67") (name "/VB_FB") (class "Default")
      (node (ref "C16") (pin "1") (pintype "passive"))
      (node (ref "R10") (pin "1") (pinfunction "1_1") (pintype "passive"))
      (node (ref "R7") (pin "2") (pinfunction "2_2") (pintype "passive"))
      (node (ref "U2") (pin "3") (pinfunction "IO_3") (pintype "passive"))
      (node (ref "U4") (pin "8") (pinfunction "ADCINA1_8") (pintype "passive"))
    )
    (net (code "68") (name "/VCPH") (class "Default")
      (node (ref "C6") (pin "1") (pintype "passive"))
      (node (ref "U1") (pin "38") (pinfunction "VCPH_38") (pintype "power_in"))
    )
    (net (code "69") (name "/VCP_LSD") (class "Default")
      (node (ref "C7") (pin "2") (pintype "passive"))
      (node (ref "U1") (pin "37") (pinfunction "VCP_LSD_37") (pintype "power_in"))
    )
    (net (code "70") (name "/VC_FB") (class "Default")
      (node (ref "C17") (pin "1") (pintype "passive"))
      (node (ref "R11") (pin "1") (pinfunction "1_1") (pintype "passive"))
      (node (ref "R8") (pin "2") (pinfunction "2_2") (pintype "passive"))
      (node (ref "U2") (pin "1") (pinfunction "IO_1") (pintype "passive"))
      (node (ref "U4") (pin "10") (pinfunction "ADCINA0_10") (pintype "passive"))
    )
    (net (code "71") (name "/VDD1") (class "Default")
      (node (ref "C30") (pin "1") (pintype "passive"))
      (node (ref "U4") (pin "32") (pinfunction "VDD1_32") (pintype "passive"))
    )
    (net (code "72") (name "/VDD2") (class "Default")
      (node (ref "C31") (pin "1") (pintype "passive"))
      (node (ref "U4") (pin "43") (pinfunction "VDD2_43") (pintype "passive"))
    )
    (net (code "73") (name "/VDDA") (class "Default")
      (node (ref "C27") (pin "1") (pintype "passive"))
      (node (ref "FB1") (pin "1") (pinfunction "1_1") (pintype "passive"))
      (node (ref "U4") (pin "11") (pinfunction "VDDA_11") (pintype "passive"))
    )
    (net (code "74") (name "/VDDIO") (class "Default")
      (node (ref "C32") (pin "1") (pintype "passive"))
      (node (ref "FB2") (pin "1") (pinfunction "1_1") (pintype "passive"))
      (node (ref "U4") (pin "35") (pinfunction "VDDIO_35") (pintype "passive"))
    )
    (net (code "75") (name "/VDRAIN") (class "Default")
      (node (ref "R2") (pin "1") (pinfunction "1_1") (pintype "passive"))
      (node (ref "U1") (pin "44") (pinfunction "VDRAIN_44") (pintype "power_in"))
    )
    (net (code "76") (name "/WAKE") (class "Default")
      (node (ref "U1") (pin "47") (pinfunction "WAKE_47") (pintype "input"))
      (node (ref "U4") (pin "42") (pinfunction "GPIO7_42") (pintype "passive"))
    )
    (net (code "77") (name "/Y") (class "Default")
      (node (ref "J13") (pin "6") (pinfunction "6_6") (pintype "passive"))
      (node (ref "R15") (pin "2") (pinfunction "2_2") (pintype "passive"))
      (node (ref "U3") (pin "6") (pinfunction "Y_6") (pintype "passive"))
    )
    (net (code "78") (name "/Z") (class "Default")
      (node (ref "J13") (pin "5") (pinfunction "5_5") (pintype "passive"))
      (node (ref "R15") (pin "1") (pinfunction "1_1") (pintype "passive"))
      (node (ref "U3") (pin "7") (pinfunction "Z_7") (pintype "passive"))
    )
    (net (code "79") (name "3.3V") (class "Default")
      (node (ref "C18") (pin "1") (pintype "passive"))
      (node (ref "C19") (pin "1") (pintype "passive"))
      (node (ref "C26") (pin "2") (pintype "passive"))
      (node (ref "C8") (pin "2") (pintype "passive"))
      (node (ref "FB1") (pin "2") (pinfunction "2_2") (pintype "passive"))
      (node (ref "FB2") (pin "2") (pinfunction "2_2") (pintype "passive"))
      (node (ref "J13") (pin "2") (pinfunction "2_2") (pintype "passive"))
      (node (ref "J19") (pin "2") (pinfunction "2_2") (pintype "passive"))
      (node (ref "JMP1") (pin "3") (pinfunction "3_3") (pintype "passive"))
      (node (ref "JMP2") (pin "3") (pinfunction "3_3") (pintype "passive"))
      (node (ref "JMP3") (pin "3") (pinfunction "3_3") (pintype "passive"))
      (node (ref "LED1") (pin "A") (pinfunction "A_A") (pintype "passive"))
      (node (ref "LED3") (pin "A") (pinfunction "A_A") (pintype "passive"))
      (node (ref "R1") (pin "1") (pinfunction "1_1") (pintype "passive"))
      (node (ref "R13") (pin "1") (pinfunction "1_1") (pintype "passive"))
      (node (ref "R21") (pin "2") (pinfunction "2_2") (pintype "passive"))
      (node (ref "U1") (pin "48") (pinfunction "VREG/VREF_48") (pintype "power_in"))
      (node (ref "U2") (pin "5") (pinfunction "VP_5") (pintype "passive"))
      (node (ref "U3") (pin "10") (pinfunction "VCC_10") (pintype "passive"))
    )
    (net (code "80") (name "16V") (class "Default")
      (node (ref "C12") (pin "1") (pintype "passive"))
      (node (ref "C13") (pin "1") (pintype "passive"))
      (node (ref "C14") (pin "1") (pintype "passive"))
      (node (ref "C20") (pin "1") (pintype "passive"))
      (node (ref "C21") (pin "1") (pintype "passive"))
      (node (ref "C5") (pin "2") (pintype "passive"))
      (node (ref "C6") (pin "2") (pintype "passive"))
      (node (ref "J17") (pin "1") (pinfunction "1_1") (pintype "passive"))
      (node (ref "Q1") (pin "D") (pinfunction "D_D") (pintype "passive"))
      (node (ref "Q3") (pin "D") (pinfunction "D_D") (pintype "passive"))
      (node (ref "Q5") (pin "D") (pinfunction "D_D") (pintype "passive"))
      (node (ref "R17") (pin "2") (pinfunction "2_2") (pintype "passive"))
      (node (ref "R2") (pin "2") (pinfunction "2_2") (pintype "passive"))
      (node (ref "R25") (pin "2") (pinfunction "2_2") (pintype "passive"))
      (node (ref "U1") (pin "41") (pinfunction "PVDD_41") (pintype "power_in"))
    )
    (net (code "81") (name "GND") (class "Default")
      (node (ref "C1") (pin "1") (pintype "passive"))
      (node (ref "C12") (pin "2") (pintype "passive"))
      (node (ref "C13") (pin "2") (pintype "passive"))
      (node (ref "C14") (pin "2") (pintype "passive"))
      (node (ref "C15") (pin "2") (pintype "passive"))
      (node (ref "C16") (pin "2") (pintype "passive"))
      (node (ref "C17") (pin "2") (pintype "passive"))
      (node (ref "C18") (pin "2") (pintype "passive"))
      (node (ref "C19") (pin "2") (pintype "passive"))
      (node (ref "C2") (pin "1") (pintype "passive"))
      (node (ref "C20") (pin "2") (pintype "passive"))
      (node (ref "C21") (pin "2") (pintype "passive"))
      (node (ref "C23") (pin "2") (pintype "passive"))
      (node (ref "C24") (pin "2") (pintype "passive"))
      (node (ref "C25") (pin "2") (pintype "passive"))
      (node (ref "C26") (pin "1") (pintype "passive"))
      (node (ref "C27") (pin "2") (pintype "passive"))
      (node (ref "C29") (pin "2") (pintype "passive"))
      (node (ref "C30") (pin "2") (pintype "passive"))
      (node (ref "C31") (pin "2") (pintype "passive"))
      (node (ref "C32") (pin "2") (pintype "passive"))
      (node (ref "C5") (pin "1") (pintype "passive"))
      (node (ref "C7") (pin "1") (pintype "passive"))
      (node (ref "C8") (pin "1") (pintype "passive"))
      (node (ref "J12") (pin "2") (pinfunction "2_2") (pintype "passive"))
      (node (ref "J13") (pin "1") (pinfunction "1_1") (pintype "passive"))
      (node (ref "J18") (pin "1") (pinfunction "1_1") (pintype "passive"))
      (node (ref "J19") (pin "1") (pinfunction "1_1") (pintype "passive"))
      (node (ref "J19") (pin "8") (pinfunction "8_8") (pintype "passive"))
      (node (ref "J4") (pin "2") (pinfunction "2_2") (pintype "passive"))
      (node (ref "J8") (pin "2") (pinfunction "2_2") (pintype "passive"))
      (node (ref "JMP1") (pin "1") (pinfunction "1_1") (pintype "passive"))
      (node (ref "JMP2") (pin "1") (pinfunction "1_1") (pintype "passive"))
      (node (ref "JMP3") (pin "1") (pinfunction "1_1") (pintype "passive"))
      (node (ref "LED2") (pin "K") (pinfunction "K_K") (pintype "passive"))
      (node (ref "R16") (pin "1") (pinfunction "1_1") (pintype "passive"))
      (node (ref "R18") (pin "1") (pinfunction "1_1") (pintype "passive"))
      (node (ref "R26") (pin "1") (pinfunction "1_1") (pintype "passive"))
      (node (ref "R27") (pin "2") (pinfunction "2_2") (pintype "passive"))
      (node (ref "R3") (pin "2") (pinfunction "2_2") (pintype "passive"))
      (node (ref "R4") (pin "2") (pinfunction "2_2") (pintype "passive"))
      (node (ref "R5") (pin "2") (pinfunction "2_2") (pintype "passive"))
      (node (ref "R6") (pin "1") (pinfunction "1_1") (pintype "passive"))
      (node (ref "R7") (pin "1") (pinfunction "1_1") (pintype "passive"))
      (node (ref "R8") (pin "1") (pinfunction "1_1") (pintype "passive"))
      (node (ref "U1") (pin "14") (pinfunction "GND_14") (pintype "power_in"))
      (node (ref "U1") (pin "45") (pinfunction "GND_45") (pintype "power_in"))
      (node (ref "U1") (pin "49") (pinfunction "PWPD_49") (pintype "power_in"))
      (node (ref "U2") (pin "2") (pinfunction "VN_2") (pintype "passive"))
      (node (ref "U3") (pin "5") (pinfunction "GND_5") (pintype "passive"))
      (node (ref "U4") (pin "12") (pinfunction "VSSA_12") (pintype "passive"))
      (node (ref "U4") (pin "14") (pinfunction "ADCINB2_14") (pintype "passive"))
      (node (ref "U4") (pin "30") (pinfunction "TEST_30") (pintype "passive"))
      (node (ref "U4") (pin "33") (pinfunction "VSS1_33") (pintype "passive"))
      (node (ref "U4") (pin "34") (pinfunction "~{VREGENZ}_34") (pintype "passive"))
      (node (ref "U4") (pin "36") (pinfunction "GPIO33_36") (pintype "passive"))
      (node (ref "U4") (pin "4") (pinfunction "ADCINA6_4") (pintype "passive"))
      (node (ref "U4") (pin "44") (pinfunction "VSS2_44") (pintype "passive"))
      (node (ref "U4") (pin "5") (pinfunction "ADCINA4_5") (pintype "passive"))
      (node (ref "U4") (pin "9") (pinfunction "ADCINA2_9") (pintype "passive"))
    )
    (net (code "82") (name "Net-(JMP1-Pad2)") (class "Default")
      (node (ref "JMP1") (pin "2") (pinfunction "2_2") (pintype "passive"))
      (node (ref "R23") (pin "1") (pinfunction "1_1") (pintype "passive"))
    )
    (net (code "83") (name "Net-(JMP2-Pad2)") (class "Default")
      (node (ref "JMP2") (pin "2") (pinfunction "2_2") (pintype "passive"))
      (node (ref "R24") (pin "1") (pinfunction "1_1") (pintype "passive"))
    )
    (net (code "84") (name "Net-(JMP3-Pad2)") (class "Default")
      (node (ref "JMP3") (pin "2") (pinfunction "2_2") (pintype "passive"))
      (node (ref "R28") (pin "1") (pinfunction "1_1") (pintype "passive"))
    )
    (net (code "85") (name "Net-(LED1-PadK)") (class "Default")
      (node (ref "LED1") (pin "K") (pinfunction "K_K") (pintype "passive"))
      (node (ref "R12") (pin "1") (pinfunction "1_1") (pintype "passive"))
    )
    (net (code "86") (name "Net-(LED2-PadA)") (class "Default")
      (node (ref "LED2") (pin "A") (pinfunction "A_A") (pintype "passive"))
      (node (ref "R17") (pin "1") (pinfunction "1_1") (pintype "passive"))
    )
    (net (code "87") (name "Net-(LED3-PadK)") (class "Default")
      (node (ref "LED3") (pin "K") (pinfunction "K_K") (pintype "passive"))
      (node (ref "R16") (pin "2") (pinfunction "2_2") (pintype "passive"))
    )
    (net (code "88") (name "unconnected-(U4-X1-Pad45)") (class "Default")
      (node (ref "U4") (pin "45") (pinfunction "X1_45") (pintype "passive"))
    )
    (net (code "89") (name "unconnected-(U4-X2-Pad46)") (class "Default")
      (node (ref "U4") (pin "46") (pinfunction "X2_46") (pintype "passive"))
    )
  )
)
